# sersors.net
KiCad netlist of a schematic drawn in EAGLE
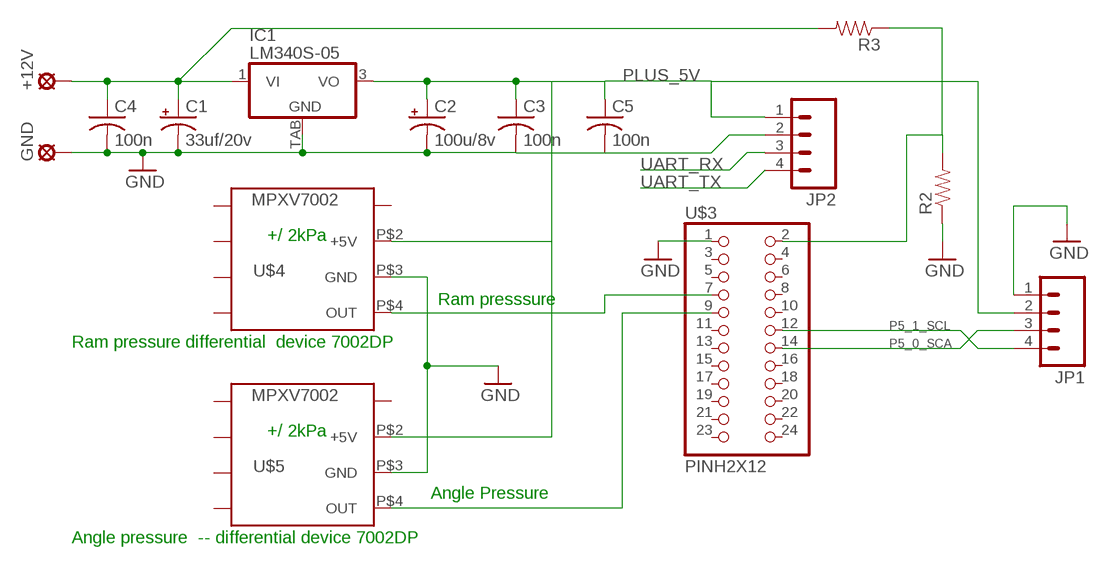
[diagram p0: schematic, sheet 1]

(export (version "E")
  (design (tool "Eeschema 10.0.6"))
  (components
    (comp (ref "+12V")
      (value "LSP10")
      (footprint "eagle-import:LSP10")
      (libsource (lib "eagle-import") (part "LSP10"))
    )
    (comp (ref "C1")
      (value "33uf/20v")
      (footprint "eagle-import:SMC_D")
      (libsource (lib "eagle-import") (part "CPOL-USSMCD"))
    )
    (comp (ref "C2")
      (value "100u/8v")
      (footprint "eagle-import:SMC_D")
      (libsource (lib "eagle-import") (part "CPOL-USSMCD"))
    )
    (comp (ref "C3")
      (value "100n")
      (footprint "eagle-import:C1206K")
      (libsource (lib "eagle-import") (part "C-USC1206K"))
    )
    (comp (ref "C4")
      (value "100n")
      (footprint "eagle-import:C1206K")
      (libsource (lib "eagle-import") (part "C-USC1206K"))
    )
    (comp (ref "C5")
      (value "100n")
      (footprint "eagle-import:C1206K")
      (libsource (lib "eagle-import") (part "C-USC1206K"))
    )
    (comp (ref "GND")
      (value "LSP10")
      (footprint "eagle-import:LSP10")
      (libsource (lib "eagle-import") (part "LSP10"))
    )
    (comp (ref "IC1")
      (value "LM340S-05")
      (footprint "eagle-import:TO263-3")
      (libsource (lib "eagle-import") (part "LM340?-S05"))
    )
    (comp (ref "JP1")
      (value "M04PTH")
      (footprint "eagle-import:1X04")
      (libsource (lib "eagle-import") (part "M04PTH"))
    )
    (comp (ref "JP2")
      (value "M04PTH")
      (footprint "eagle-import:1X04")
      (libsource (lib "eagle-import") (part "M04PTH"))
    )
    (comp (ref "R2")
      (value "RESISTOR0603-RES")
      (footprint "eagle-import:0603-RES")
      (libsource (lib "eagle-import") (part "RESISTOR0603-RES"))
    )
    (comp (ref "R3")
      (value "RESISTOR0603-RES")
      (footprint "eagle-import:0603-RES")
      (libsource (lib "eagle-import") (part "RESISTOR0603-RES"))
    )
    (comp (ref "U$3")
      (value "PINH2X12")
      (footprint "eagle-import:2X12")
      (libsource (lib "eagle-import") (part "PINH2X12"))
    )
    (comp (ref "U$4")
      (value "MPXV7002")
      (footprint "eagle-import:MPXV")
      (libsource (lib "eagle-import") (part "MPXV7002"))
    )
    (comp (ref "U$5")
      (value "MPXV7002")
      (footprint "eagle-import:MPXV")
      (libsource (lib "eagle-import") (part "MPXV7002"))
    )
  )
  (nets
    (net (code "1") (name "/P5_0_SCA") (class "Default")
      (node (ref "JP1") (pin "3") (pinfunction "3_3") (pintype "passive"))
      (node (ref "U$3") (pin "14") (pinfunction "14_14") (pintype "passive"))
    )
    (net (code "2") (name "/P5_1_SCL") (class "Default")
      (node (ref "JP1") (pin "4") (pinfunction "4_4") (pintype "passive"))
      (node (ref "U$3") (pin "12") (pinfunction "12_12") (pintype "passive"))
    )
    (net (code "3") (name "/PLUS_5V") (class "Default")
      (node (ref "C2") (pin "+") (pinfunction "+_+") (pintype "passive"))
      (node (ref "C3") (pin "1") (pinfunction "1_1") (pintype "passive"))
      (node (ref "C5") (pin "1") (pinfunction "1_1") (pintype "passive"))
      (node (ref "IC1") (pin "3") (pinfunction "VO_3") (pintype "passive"))
      (node (ref "JP1") (pin "2") (pinfunction "2_2") (pintype "passive"))
      (node (ref "JP2") (pin "1") (pinfunction "1_1") (pintype "passive"))
      (node (ref "U$4") (pin "P$2") (pinfunction "+5V_P$2") (pintype "power_in"))
      (node (ref "U$5") (pin "P$2") (pinfunction "+5V_P$2") (pintype "power_in"))
    )
    (net (code "4") (name "/UART_RX") (class "Default")
      (node (ref "JP2") (pin "3") (pinfunction "3_3") (pintype "passive"))
    )
    (net (code "5") (name "/UART_TX") (class "Default")
      (node (ref "JP2") (pin "4") (pinfunction "4_4") (pintype "passive"))
    )
    (net (code "6") (name "GND") (class "Default")
      (node (ref "C1") (pin "-") (pinfunction "-_-") (pintype "passive"))
      (node (ref "C2") (pin "-") (pinfunction "-_-") (pintype "passive"))
      (node (ref "C3") (pin "2") (pinfunction "2_2") (pintype "passive"))
      (node (ref "C4") (pin "2") (pinfunction "2_2") (pintype "passive"))
      (node (ref "C5") (pin "2") (pinfunction "2_2") (pintype "passive"))
      (node (ref "GND") (pin "MP") (pinfunction "MP_MP") (pintype "passive"))
      (node (ref "IC1") (pin "TAB") (pinfunction "GND_TAB") (pintype "passive"))
      (node (ref "JP1") (pin "1") (pinfunction "1_1") (pintype "passive"))
      (node (ref "JP2") (pin "2") (pinfunction "2_2") (pintype "passive"))
      (node (ref "R2") (pin "1") (pinfunction "1_1") (pintype "passive"))
      (node (ref "U$3") (pin "1") (pinfunction "1_1") (pintype "passive"))
      (node (ref "U$4") (pin "P$3") (pinfunction "GND_P$3") (pintype "power_in"))
      (node (ref "U$5") (pin "P$3") (pinfunction "GND_P$3") (pintype "power_in"))
    )
    (net (code "7") (name "Net-(IC1-VI)") (class "Default")
      (node (ref "+12V") (pin "MP") (pinfunction "MP_MP") (pintype "passive"))
      (node (ref "C1") (pin "+") (pinfunction "+_+") (pintype "passive"))
      (node (ref "C4") (pin "1") (pinfunction "1_1") (pintype "passive"))
      (node (ref "IC1") (pin "1") (pinfunction "VI_1") (pintype "input"))
      (node (ref "R3") (pin "2") (pinfunction "2_2") (pintype "passive"))
    )
    (net (code "8") (name "Net-(R2-Pad2)") (class "Default")
      (node (ref "R2") (pin "2") (pinfunction "2_2") (pintype "passive"))
      (node (ref "R3") (pin "1") (pinfunction "1_1") (pintype "passive"))
      (node (ref "U$3") (pin "2") (pinfunction "2_2") (pintype "passive"))
    )
    (net (code "9") (name "Net-(U$4-OUT)") (class "Default")
      (node (ref "U$3") (pin "7") (pinfunction "7_7") (pintype "passive"))
      (node (ref "U$4") (pin "P$4") (pinfunction "OUT_P$4") (pintype "output"))
    )
    (net (code "10") (name "Net-(U$5-OUT)") (class "Default")
      (node (ref "U$3") (pin "9") (pinfunction "9_9") (pintype "passive"))
      (node (ref "U$5") (pin "P$4") (pinfunction "OUT_P$4") (pintype "output"))
    )
    (net (code "11") (name "unconnected-(U$3-Pad3)") (class "Default")
      (node (ref "U$3") (pin "3") (pinfunction "3_3") (pintype "passive"))
    )
    (net (code "12") (name "unconnected-(U$3-Pad4)") (class "Default")
      (node (ref "U$3") (pin "4") (pinfunction "4_4") (pintype "passive"))
    )
    (net (code "13") (name "unconnected-(U$3-Pad5)") (class "Default")
      (node (ref "U$3") (pin "5") (pinfunction "5_5") (pintype "passive"))
    )
    (net (code "14") (name "unconnected-(U$3-Pad6)") (class "Default")
      (node (ref "U$3") (pin "6") (pinfunction "6_6") (pintype "passive"))
    )
    (net (code "15") (name "unconnected-(U$3-Pad8)") (class "Default")
      (node (ref "U$3") (pin "8") (pinfunction "8_8") (pintype "passive"))
    )
    (net (code "16") (name "unconnected-(U$3-Pad10)") (class "Default")
      (node (ref "U$3") (pin "10") (pinfunction "10_10") (pintype "passive"))
    )
    (net (code "17") (name "unconnected-(U$3-Pad11)") (class "Default")
      (node (ref "U$3") (pin "11") (pinfunction "11_11") (pintype "passive"))
    )
    (net (code "18") (name "unconnected-(U$3-Pad13)") (class "Default")
      (node (ref "U$3") (pin "13") (pinfunction "13_13") (pintype "passive"))
    )
    (net (code "19") (name "unconnected-(U$3-Pad15)") (class "Default")
      (node (ref "U$3") (pin "15") (pinfunction "15_15") (pintype "passive"))
    )
    (net (code "20") (name "unconnected-(U$3-Pad16)") (class "Default")
      (node (ref "U$3") (pin "16") (pinfunction "16_16") (pintype "passive"))
    )
    (net (code "21") (name "unconnected-(U$3-Pad17)") (class "Default")
      (node (ref "U$3") (pin "17") (pinfunction "17_17") (pintype "passive"))
    )
    (net (code "22") (name "unconnected-(U$3-Pad18)") (class "Default")
      (node (ref "U$3") (pin "18") (pinfunction "18_18") (pintype "passive"))
    )
    (net (code "23") (name "unconnected-(U$3-Pad19)") (class "Default")
      (node (ref "U$3") (pin "19") (pinfunction "19_19") (pintype "passive"))
    )
    (net (code "24") (name "unconnected-(U$3-Pad20)") (class "Default")
      (node (ref "U$3") (pin "20") (pinfunction "20_20") (pintype "passive"))
    )
    (net (code "25") (name "unconnected-(U$3-Pad21)") (class "Default")
      (node (ref "U$3") (pin "21") (pinfunction "21_21") (pintype "passive"))
    )
    (net (code "26") (name "unconnected-(U$3-Pad22)") (class "Default")
      (node (ref "U$3") (pin "22") (pinfunction "22_22") (pintype "passive"))
    )
    (net (code "27") (name "unconnected-(U$3-Pad23)") (class "Default")
      (node (ref "U$3") (pin "23") (pinfunction "23_23") (pintype "passive"))
    )
    (net (code "28") (name "unconnected-(U$3-Pad24)") (class "Default")
      (node (ref "U$3") (pin "24") (pinfunction "24_24") (pintype "passive"))
    )
    (net (code "29") (name "unconnected-(U$4-PadP$1)") (class "Default")
      (node (ref "U$4") (pin "P$1") (pinfunction "P$1_P$1") (pintype "no_connect"))
    )
    (net (code "30") (name "unconnected-(U$4-PadP$5)") (class "Default")
      (node (ref "U$4") (pin "P$5") (pinfunction "P$5_P$5") (pintype "no_connect"))
    )
    (net (code "31") (name "unconnected-(U$4-PadP$6)") (class "Default")
      (node (ref "U$4") (pin "P$6") (pinfunction "P$6_P$6") (pintype "no_connect"))
    )
    (net (code "32") (name "unconnected-(U$4-PadP$7)") (class "Default")
      (node (ref "U$4") (pin "P$7") (pinfunction "P$7_P$7") (pintype "no_connect"))
    )
    (net (code "33") (name "unconnected-(U$4-PadP$8)") (class "Default")
      (node (ref "U$4") (pin "P$8") (pinfunction "P$8_P$8") (pintype "no_connect"))
    )
    (net (code "34") (name "unconnected-(U$5-PadP$1)") (class "Default")
      (node (ref "U$5") (pin "P$1") (pinfunction "P$1_P$1") (pintype "no_connect"))
    )
    (net (code "35") (name "unconnected-(U$5-PadP$5)") (class "Default")
      (node (ref "U$5") (pin "P$5") (pinfunction "P$5_P$5") (pintype "no_connect"))
    )
    (net (code "36") (name "unconnected-(U$5-PadP$6)") (class "Default")
      (node (ref "U$5") (pin "P$6") (pinfunction "P$6_P$6") (pintype "no_connect"))
    )
    (net (code "37") (name "unconnected-(U$5-PadP$7)") (class "Default")
      (node (ref "U$5") (pin "P$7") (pinfunction "P$7_P$7") (pintype "no_connect"))
    )
    (net (code "38") (name "unconnected-(U$5-PadP$8)") (class "Default")
      (node (ref "U$5") (pin "P$8") (pinfunction "P$8_P$8") (pintype "no_connect"))
    )
  )
)
